# 7segement4digits1badidea-shield-mk-5.net
KiCad netlist of a schematic drawn in EAGLE
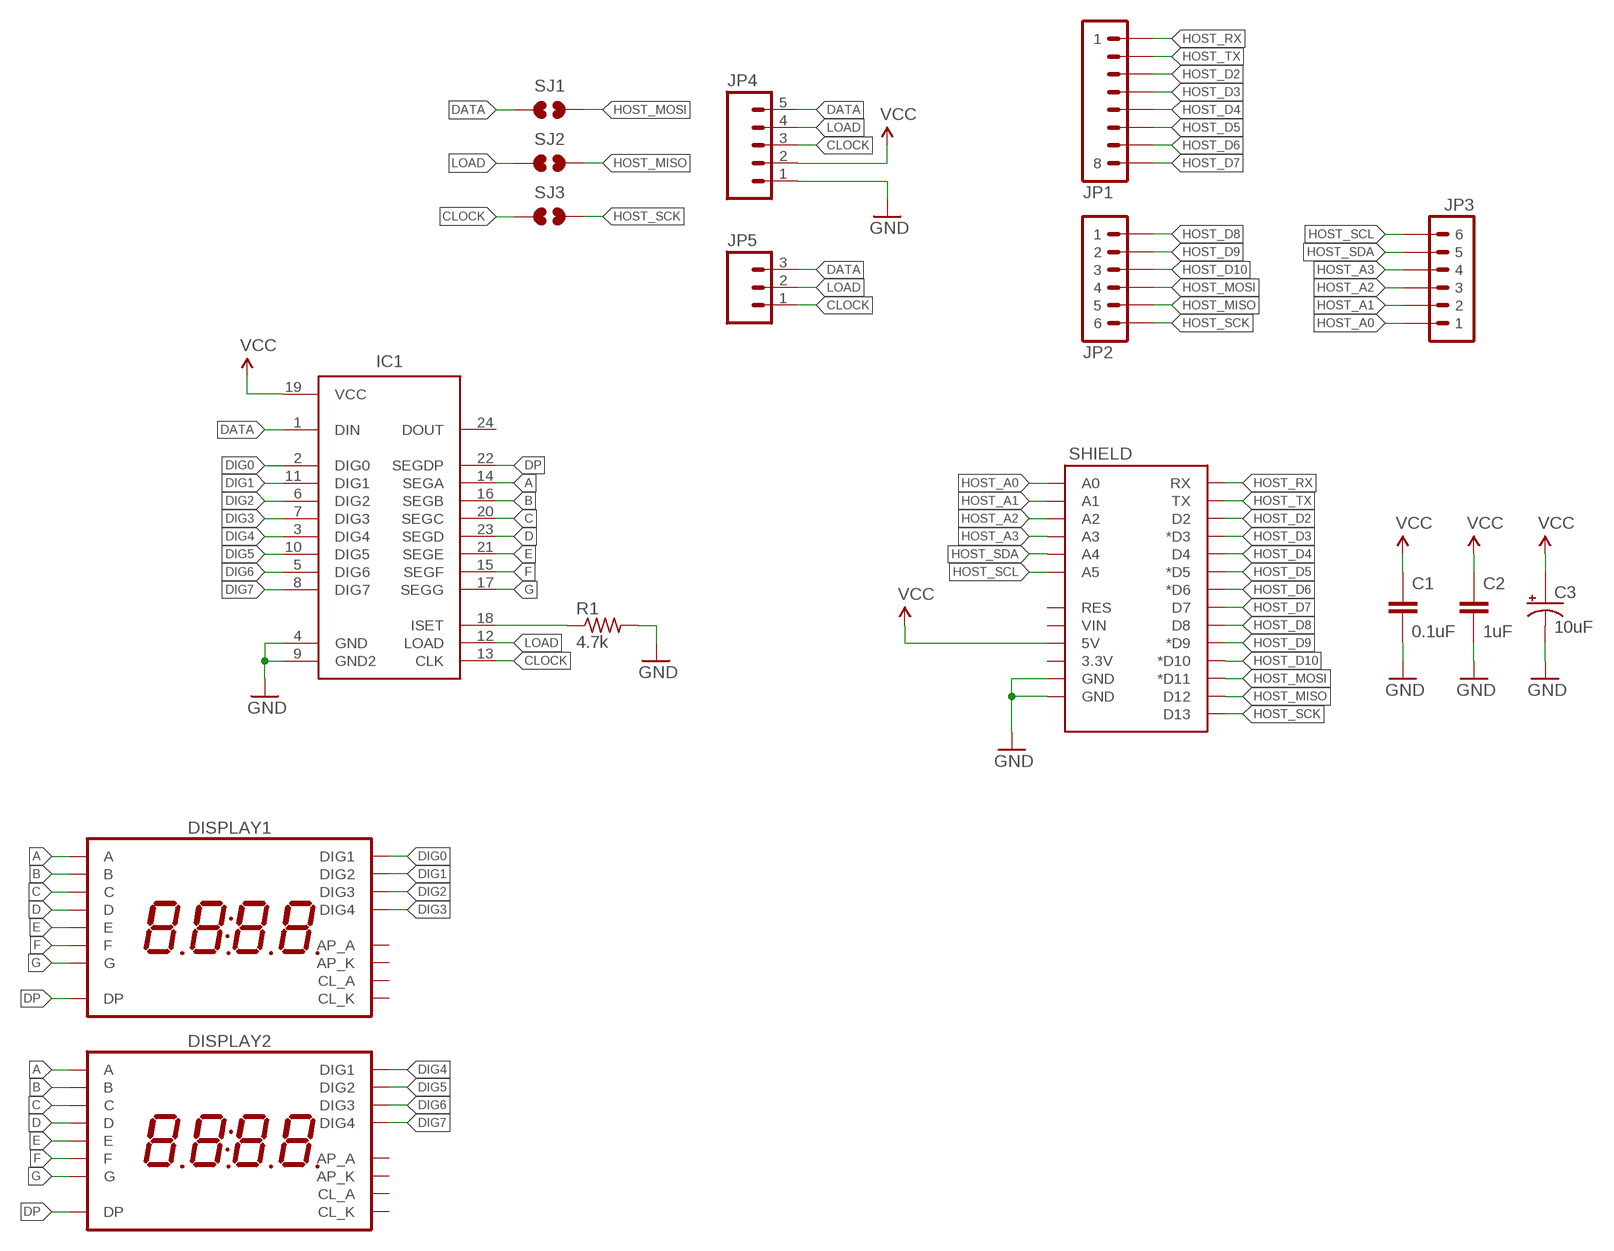
[diagram p0: schematic, sheet 1]

(export (version "E")
  (design (tool "Eeschema 10.0.6"))
  (components
    (comp (ref "C1")
      (value "0.1uF")
      (footprint "eagle-import:C025-024X044")
      (libsource (lib "eagle-import") (part "CAPACITOR-CERAMIC025-024X044"))
    )
    (comp (ref "C2")
      (value "1uF")
      (footprint "eagle-import:C025-024X044")
      (libsource (lib "eagle-import") (part "CAPACITOR-CERAMIC025-024X044"))
    )
    (comp (ref "C3")
      (value "10uF")
      (footprint "eagle-import:E2,5-6")
      (libsource (lib "eagle-import") (part "CAPACITOR-POLARIZEDE2.5-6"))
    )
    (comp (ref "DISPLAY1")
      (value "7SEG_4DIGIT_10MM")
      (footprint "eagle-import:7SEG_4DIG_10MM")
      (libsource (lib "eagle-import") (part "7SEG_4DIGIT_10MM"))
    )
    (comp (ref "DISPLAY2")
      (value "7SEG_4DIGIT_10MM")
      (footprint "eagle-import:7SEG_4DIG_10MM")
      (libsource (lib "eagle-import") (part "7SEG_4DIGIT_10MM"))
    )
    (comp (ref "IC1")
      (value "MAX7219DIP")
      (footprint "eagle-import:DIL24")
      (libsource (lib "eagle-import") (part "MAX7219DIP"))
    )
    (comp (ref "JP1")
      (value "M08NOT-SHITTY-NO-SILK")
      (footprint "eagle-import:1X08_NS")
      (libsource (lib "eagle-import") (part "M08NOT-SHITTY-NO-SILK"))
    )
    (comp (ref "JP2")
      (value "M06SIP")
      (footprint "eagle-import:1X06")
      (libsource (lib "eagle-import") (part "M06SIP"))
    )
    (comp (ref "JP3")
      (value "M06SIP")
      (footprint "eagle-import:1X06")
      (libsource (lib "eagle-import") (part "M06SIP"))
    )
    (comp (ref "JP4")
      (value "M05PTH")
      (footprint "eagle-import:1X05")
      (libsource (lib "eagle-import") (part "M05PTH"))
    )
    (comp (ref "JP5")
      (value "M031X03_NO_SILK")
      (footprint "eagle-import:1X03_NO_SILK")
      (libsource (lib "eagle-import") (part "M031X03_NO_SILK"))
    )
    (comp (ref "R1")
      (value "4.7k")
      (footprint "eagle-import:RESISTOR-AXIAL-PTH-5.08MM")
      (libsource (lib "eagle-import") (part "RESISTORPTH-AXIAL-5.08MM"))
    )
    (comp (ref "SHIELD")
      (value "ARDUINO_SHIELD_SMALLERNEKKID")
      (footprint "eagle-import:ARDUINO_SHIELD_SMALLER_NEKKID")
      (libsource (lib "eagle-import") (part "ARDUINO_SHIELD_SMALLERNEKKID"))
    )
    (comp (ref "SJ1")
      (value "JUMPER-PAD-2-NOYES_SILK")
      (footprint "eagle-import:PAD-JUMPER-2-NO_YES_SILK")
      (libsource (lib "eagle-import") (part "JUMPER-PAD-2-NOYES_SILK"))
    )
    (comp (ref "SJ2")
      (value "JUMPER-PAD-2-NOYES_SILK")
      (footprint "eagle-import:PAD-JUMPER-2-NO_YES_SILK")
      (libsource (lib "eagle-import") (part "JUMPER-PAD-2-NOYES_SILK"))
    )
    (comp (ref "SJ3")
      (value "JUMPER-PAD-2-NOYES_SILK")
      (footprint "eagle-import:PAD-JUMPER-2-NO_YES_SILK")
      (libsource (lib "eagle-import") (part "JUMPER-PAD-2-NOYES_SILK"))
    )
  )
  (nets
    (net (code "1") (name "A") (class "Default")
      (node (ref "DISPLAY1") (pin "14") (pinfunction "A_14") (pintype "passive"))
      (node (ref "DISPLAY2") (pin "14") (pinfunction "A_14") (pintype "passive"))
      (node (ref "IC1") (pin "14") (pinfunction "SEGA_14") (pintype "bidirectional"))
    )
    (net (code "2") (name "B") (class "Default")
      (node (ref "DISPLAY1") (pin "16") (pinfunction "B_16") (pintype "passive"))
      (node (ref "DISPLAY2") (pin "16") (pinfunction "B_16") (pintype "passive"))
      (node (ref "IC1") (pin "16") (pinfunction "SEGB_16") (pintype "bidirectional"))
    )
    (net (code "3") (name "C") (class "Default")
      (node (ref "DISPLAY1") (pin "13") (pinfunction "C_13") (pintype "passive"))
      (node (ref "DISPLAY2") (pin "13") (pinfunction "C_13") (pintype "passive"))
      (node (ref "IC1") (pin "20") (pinfunction "SEGC_20") (pintype "bidirectional"))
    )
    (net (code "4") (name "CLOCK") (class "Default")
      (node (ref "IC1") (pin "13") (pinfunction "CLK_13") (pintype "bidirectional"))
      (node (ref "JP4") (pin "3") (pinfunction "3_3") (pintype "passive"))
      (node (ref "JP5") (pin "1") (pinfunction "1_1") (pintype "passive"))
      (node (ref "SJ3") (pin "1") (pinfunction "1_1") (pintype "passive"))
    )
    (net (code "5") (name "D") (class "Default")
      (node (ref "DISPLAY1") (pin "3") (pinfunction "D_3") (pintype "passive"))
      (node (ref "DISPLAY2") (pin "3") (pinfunction "D_3") (pintype "passive"))
      (node (ref "IC1") (pin "23") (pinfunction "SEGD_23") (pintype "bidirectional"))
    )
    (net (code "6") (name "DATA") (class "Default")
      (node (ref "IC1") (pin "1") (pinfunction "DIN_1") (pintype "bidirectional"))
      (node (ref "JP4") (pin "5") (pinfunction "5_5") (pintype "passive"))
      (node (ref "JP5") (pin "3") (pinfunction "3_3") (pintype "passive"))
      (node (ref "SJ1") (pin "1") (pinfunction "1_1") (pintype "passive"))
    )
    (net (code "7") (name "DIG0") (class "Default")
      (node (ref "DISPLAY1") (pin "1") (pinfunction "DIG1_1") (pintype "passive"))
      (node (ref "IC1") (pin "2") (pinfunction "DIG0_2") (pintype "bidirectional"))
    )
    (net (code "8") (name "DIG1") (class "Default")
      (node (ref "DISPLAY1") (pin "2") (pinfunction "DIG2_2") (pintype "passive"))
      (node (ref "IC1") (pin "11") (pinfunction "DIG1_11") (pintype "bidirectional"))
    )
    (net (code "9") (name "DIG2") (class "Default")
      (node (ref "DISPLAY1") (pin "6") (pinfunction "DIG3_6") (pintype "passive"))
      (node (ref "IC1") (pin "6") (pinfunction "DIG2_6") (pintype "bidirectional"))
    )
    (net (code "10") (name "DIG3") (class "Default")
      (node (ref "DISPLAY1") (pin "8") (pinfunction "DIG4_8") (pintype "passive"))
      (node (ref "IC1") (pin "7") (pinfunction "DIG3_7") (pintype "bidirectional"))
    )
    (net (code "11") (name "DIG4") (class "Default")
      (node (ref "DISPLAY2") (pin "1") (pinfunction "DIG1_1") (pintype "passive"))
      (node (ref "IC1") (pin "3") (pinfunction "DIG4_3") (pintype "bidirectional"))
    )
    (net (code "12") (name "DIG5") (class "Default")
      (node (ref "DISPLAY2") (pin "2") (pinfunction "DIG2_2") (pintype "passive"))
      (node (ref "IC1") (pin "10") (pinfunction "DIG5_10") (pintype "bidirectional"))
    )
    (net (code "13") (name "DIG6") (class "Default")
      (node (ref "DISPLAY2") (pin "6") (pinfunction "DIG3_6") (pintype "passive"))
      (node (ref "IC1") (pin "5") (pinfunction "DIG6_5") (pintype "bidirectional"))
    )
    (net (code "14") (name "DIG7") (class "Default")
      (node (ref "DISPLAY2") (pin "8") (pinfunction "DIG4_8") (pintype "passive"))
      (node (ref "IC1") (pin "8") (pinfunction "DIG7_8") (pintype "bidirectional"))
    )
    (net (code "15") (name "DP") (class "Default")
      (node (ref "DISPLAY1") (pin "7") (pinfunction "DP_7") (pintype "passive"))
      (node (ref "DISPLAY2") (pin "7") (pinfunction "DP_7") (pintype "passive"))
      (node (ref "IC1") (pin "22") (pinfunction "SEGDP_22") (pintype "bidirectional"))
    )
    (net (code "16") (name "E") (class "Default")
      (node (ref "DISPLAY1") (pin "5") (pinfunction "E_5") (pintype "passive"))
      (node (ref "DISPLAY2") (pin "5") (pinfunction "E_5") (pintype "passive"))
      (node (ref "IC1") (pin "21") (pinfunction "SEGE_21") (pintype "bidirectional"))
    )
    (net (code "17") (name "F") (class "Default")
      (node (ref "DISPLAY1") (pin "11") (pinfunction "F_11") (pintype "passive"))
      (node (ref "DISPLAY2") (pin "11") (pinfunction "F_11") (pintype "passive"))
      (node (ref "IC1") (pin "15") (pinfunction "SEGF_15") (pintype "bidirectional"))
    )
    (net (code "18") (name "G") (class "Default")
      (node (ref "DISPLAY1") (pin "15") (pinfunction "G_15") (pintype "passive"))
      (node (ref "DISPLAY2") (pin "15") (pinfunction "G_15") (pintype "passive"))
      (node (ref "IC1") (pin "17") (pinfunction "SEGG_17") (pintype "bidirectional"))
    )
    (net (code "19") (name "GND") (class "Default")
      (node (ref "C1") (pin "2") (pinfunction "2_2") (pintype "passive"))
      (node (ref "C2") (pin "2") (pinfunction "2_2") (pintype "passive"))
      (node (ref "C3") (pin "-") (pinfunction "-_-") (pintype "passive"))
      (node (ref "IC1") (pin "4") (pinfunction "GND_4") (pintype "bidirectional"))
      (node (ref "IC1") (pin "9") (pinfunction "GND2_9") (pintype "bidirectional"))
      (node (ref "JP4") (pin "1") (pinfunction "1_1") (pintype "passive"))
      (node (ref "R1") (pin "P$2") (pinfunction "2_P$2") (pintype "passive"))
      (node (ref "SHIELD") (pin "GND@0") (pinfunction "GND_GND@0") (pintype "bidirectional"))
      (node (ref "SHIELD") (pin "GND@1") (pinfunction "GND_GND@1") (pintype "bidirectional"))
    )
    (net (code "20") (name "HOST_A0") (class "Default")
      (node (ref "JP3") (pin "1") (pinfunction "1_1") (pintype "passive"))
      (node (ref "SHIELD") (pin "A0") (pinfunction "A0_A0") (pintype "bidirectional"))
    )
    (net (code "21") (name "HOST_A1") (class "Default")
      (node (ref "JP3") (pin "2") (pinfunction "2_2") (pintype "passive"))
      (node (ref "SHIELD") (pin "A1") (pinfunction "A1_A1") (pintype "bidirectional"))
    )
    (net (code "22") (name "HOST_A2") (class "Default")
      (node (ref "JP3") (pin "3") (pinfunction "3_3") (pintype "passive"))
      (node (ref "SHIELD") (pin "A2") (pinfunction "A2_A2") (pintype "bidirectional"))
    )
    (net (code "23") (name "HOST_A3") (class "Default")
      (node (ref "JP3") (pin "4") (pinfunction "4_4") (pintype "passive"))
      (node (ref "SHIELD") (pin "A3") (pinfunction "A3_A3") (pintype "bidirectional"))
    )
    (net (code "24") (name "HOST_D2") (class "Default")
      (node (ref "JP1") (pin "3") (pinfunction "3_3") (pintype "passive"))
      (node (ref "SHIELD") (pin "D2") (pinfunction "D2_D2") (pintype "bidirectional"))
    )
    (net (code "25") (name "HOST_D3") (class "Default")
      (node (ref "JP1") (pin "4") (pinfunction "4_4") (pintype "passive"))
      (node (ref "SHIELD") (pin "D3") (pinfunction "*D3_D3") (pintype "bidirectional"))
    )
    (net (code "26") (name "HOST_D4") (class "Default")
      (node (ref "JP1") (pin "5") (pinfunction "5_5") (pintype "passive"))
      (node (ref "SHIELD") (pin "D4") (pinfunction "D4_D4") (pintype "bidirectional"))
    )
    (net (code "27") (name "HOST_D5") (class "Default")
      (node (ref "JP1") (pin "6") (pinfunction "6_6") (pintype "passive"))
      (node (ref "SHIELD") (pin "D5") (pinfunction "*D5_D5") (pintype "bidirectional"))
    )
    (net (code "28") (name "HOST_D6") (class "Default")
      (node (ref "JP1") (pin "7") (pinfunction "7_7") (pintype "passive"))
      (node (ref "SHIELD") (pin "D6") (pinfunction "*D6_D6") (pintype "bidirectional"))
    )
    (net (code "29") (name "HOST_D7") (class "Default")
      (node (ref "JP1") (pin "8") (pinfunction "8_8") (pintype "passive"))
      (node (ref "SHIELD") (pin "D7") (pinfunction "D7_D7") (pintype "bidirectional"))
    )
    (net (code "30") (name "HOST_D8") (class "Default")
      (node (ref "JP2") (pin "1") (pinfunction "1_1") (pintype "passive"))
      (node (ref "SHIELD") (pin "D8") (pinfunction "D8_D8") (pintype "bidirectional"))
    )
    (net (code "31") (name "HOST_D9") (class "Default")
      (node (ref "JP2") (pin "2") (pinfunction "2_2") (pintype "passive"))
      (node (ref "SHIELD") (pin "D9") (pinfunction "*D9_D9") (pintype "bidirectional"))
    )
    (net (code "32") (name "HOST_D10") (class "Default")
      (node (ref "JP2") (pin "3") (pinfunction "3_3") (pintype "passive"))
      (node (ref "SHIELD") (pin "D10") (pinfunction "*D10_D10") (pintype "bidirectional"))
    )
    (net (code "33") (name "HOST_MISO") (class "Default")
      (node (ref "JP2") (pin "5") (pinfunction "5_5") (pintype "passive"))
      (node (ref "SHIELD") (pin "D12") (pinfunction "D12_D12") (pintype "bidirectional"))
      (node (ref "SJ2") (pin "2") (pinfunction "2_2") (pintype "passive"))
    )
    (net (code "34") (name "HOST_MOSI") (class "Default")
      (node (ref "JP2") (pin "4") (pinfunction "4_4") (pintype "passive"))
      (node (ref "SHIELD") (pin "D11") (pinfunction "*D11_D11") (pintype "bidirectional"))
      (node (ref "SJ1") (pin "2") (pinfunction "2_2") (pintype "passive"))
    )
    (net (code "35") (name "HOST_RX") (class "Default")
      (node (ref "JP1") (pin "1") (pinfunction "1_1") (pintype "passive"))
      (node (ref "SHIELD") (pin "RX") (pinfunction "RX_RX") (pintype "bidirectional"))
    )
    (net (code "36") (name "HOST_SCK") (class "Default")
      (node (ref "JP2") (pin "6") (pinfunction "6_6") (pintype "passive"))
      (node (ref "SHIELD") (pin "D13") (pinfunction "D13_D13") (pintype "bidirectional"))
      (node (ref "SJ3") (pin "2") (pinfunction "2_2") (pintype "passive"))
    )
    (net (code "37") (name "HOST_SCL") (class "Default")
      (node (ref "JP3") (pin "6") (pinfunction "6_6") (pintype "passive"))
      (node (ref "SHIELD") (pin "A5") (pinfunction "A5_A5") (pintype "bidirectional"))
    )
    (net (code "38") (name "HOST_SDA") (class "Default")
      (node (ref "JP3") (pin "5") (pinfunction "5_5") (pintype "passive"))
      (node (ref "SHIELD") (pin "A4") (pinfunction "A4_A4") (pintype "bidirectional"))
    )
    (net (code "39") (name "HOST_TX") (class "Default")
      (node (ref "JP1") (pin "2") (pinfunction "2_2") (pintype "passive"))
      (node (ref "SHIELD") (pin "TX") (pinfunction "TX_TX") (pintype "bidirectional"))
    )
    (net (code "40") (name "LOAD") (class "Default")
      (node (ref "IC1") (pin "12") (pinfunction "LOAD_12") (pintype "bidirectional"))
      (node (ref "JP4") (pin "4") (pinfunction "4_4") (pintype "passive"))
      (node (ref "JP5") (pin "2") (pinfunction "2_2") (pintype "passive"))
      (node (ref "SJ2") (pin "1") (pinfunction "1_1") (pintype "passive"))
    )
    (net (code "41") (name "Net-(IC1-ISET)") (class "Default")
      (node (ref "IC1") (pin "18") (pinfunction "ISET_18") (pintype "bidirectional"))
      (node (ref "R1") (pin "P$1") (pinfunction "1_P$1") (pintype "passive"))
    )
    (net (code "42") (name "VCC") (class "Default")
      (node (ref "C1") (pin "1") (pinfunction "1_1") (pintype "passive"))
      (node (ref "C2") (pin "1") (pinfunction "1_1") (pintype "passive"))
      (node (ref "C3") (pin "+") (pinfunction "+_+") (pintype "passive"))
      (node (ref "IC1") (pin "19") (pinfunction "VCC_19") (pintype "bidirectional"))
      (node (ref "JP4") (pin "2") (pinfunction "2_2") (pintype "passive"))
      (node (ref "SHIELD") (pin "5V") (pinfunction "5V_5V") (pintype "bidirectional"))
    )
    (net (code "43") (name "unconnected-(DISPLAY1-AP_A-Pad10)") (class "Default")
      (node (ref "DISPLAY1") (pin "10") (pinfunction "AP_A_10") (pintype "bidirectional"))
    )
    (net (code "44") (name "unconnected-(DISPLAY1-AP_K-Pad9)") (class "Default")
      (node (ref "DISPLAY1") (pin "9") (pinfunction "AP_K_9") (pintype "bidirectional"))
    )
    (net (code "45") (name "unconnected-(DISPLAY1-CL_A-Pad4)") (class "Default")
      (node (ref "DISPLAY1") (pin "4") (pinfunction "CL_A_4") (pintype "passive"))
    )
    (net (code "46") (name "unconnected-(DISPLAY1-CL_K-Pad12)") (class "Default")
      (node (ref "DISPLAY1") (pin "12") (pinfunction "CL_K_12") (pintype "passive"))
    )
    (net (code "47") (name "unconnected-(DISPLAY2-AP_A-Pad10)") (class "Default")
      (node (ref "DISPLAY2") (pin "10") (pinfunction "AP_A_10") (pintype "bidirectional"))
    )
    (net (code "48") (name "unconnected-(DISPLAY2-AP_K-Pad9)") (class "Default")
      (node (ref "DISPLAY2") (pin "9") (pinfunction "AP_K_9") (pintype "bidirectional"))
    )
    (net (code "49") (name "unconnected-(DISPLAY2-CL_A-Pad4)") (class "Default")
      (node (ref "DISPLAY2") (pin "4") (pinfunction "CL_A_4") (pintype "passive"))
    )
    (net (code "50") (name "unconnected-(DISPLAY2-CL_K-Pad12)") (class "Default")
      (node (ref "DISPLAY2") (pin "12") (pinfunction "CL_K_12") (pintype "passive"))
    )
    (net (code "51") (name "unconnected-(IC1-DOUT-Pad24)") (class "Default")
      (node (ref "IC1") (pin "24") (pinfunction "DOUT_24") (pintype "bidirectional"))
    )
    (net (code "52") (name "unconnected-(SHIELD-Pad3.3V)") (class "Default")
      (node (ref "SHIELD") (pin "3.3V") (pinfunction "3.3V_3.3V") (pintype "bidirectional"))
    )
    (net (code "53") (name "unconnected-(SHIELD-PadRES)") (class "Default")
      (node (ref "SHIELD") (pin "RES") (pinfunction "RES_RES") (pintype "bidirectional"))
    )
    (net (code "54") (name "unconnected-(SHIELD-PadVIN)") (class "Default")
      (node (ref "SHIELD") (pin "VIN") (pinfunction "VIN_VIN") (pintype "bidirectional"))
    )
  )
)
